# SCH_Hackpad-c-pad_2026-07-27.net
KiCad netlist of a schematic drawn in EasyEDA
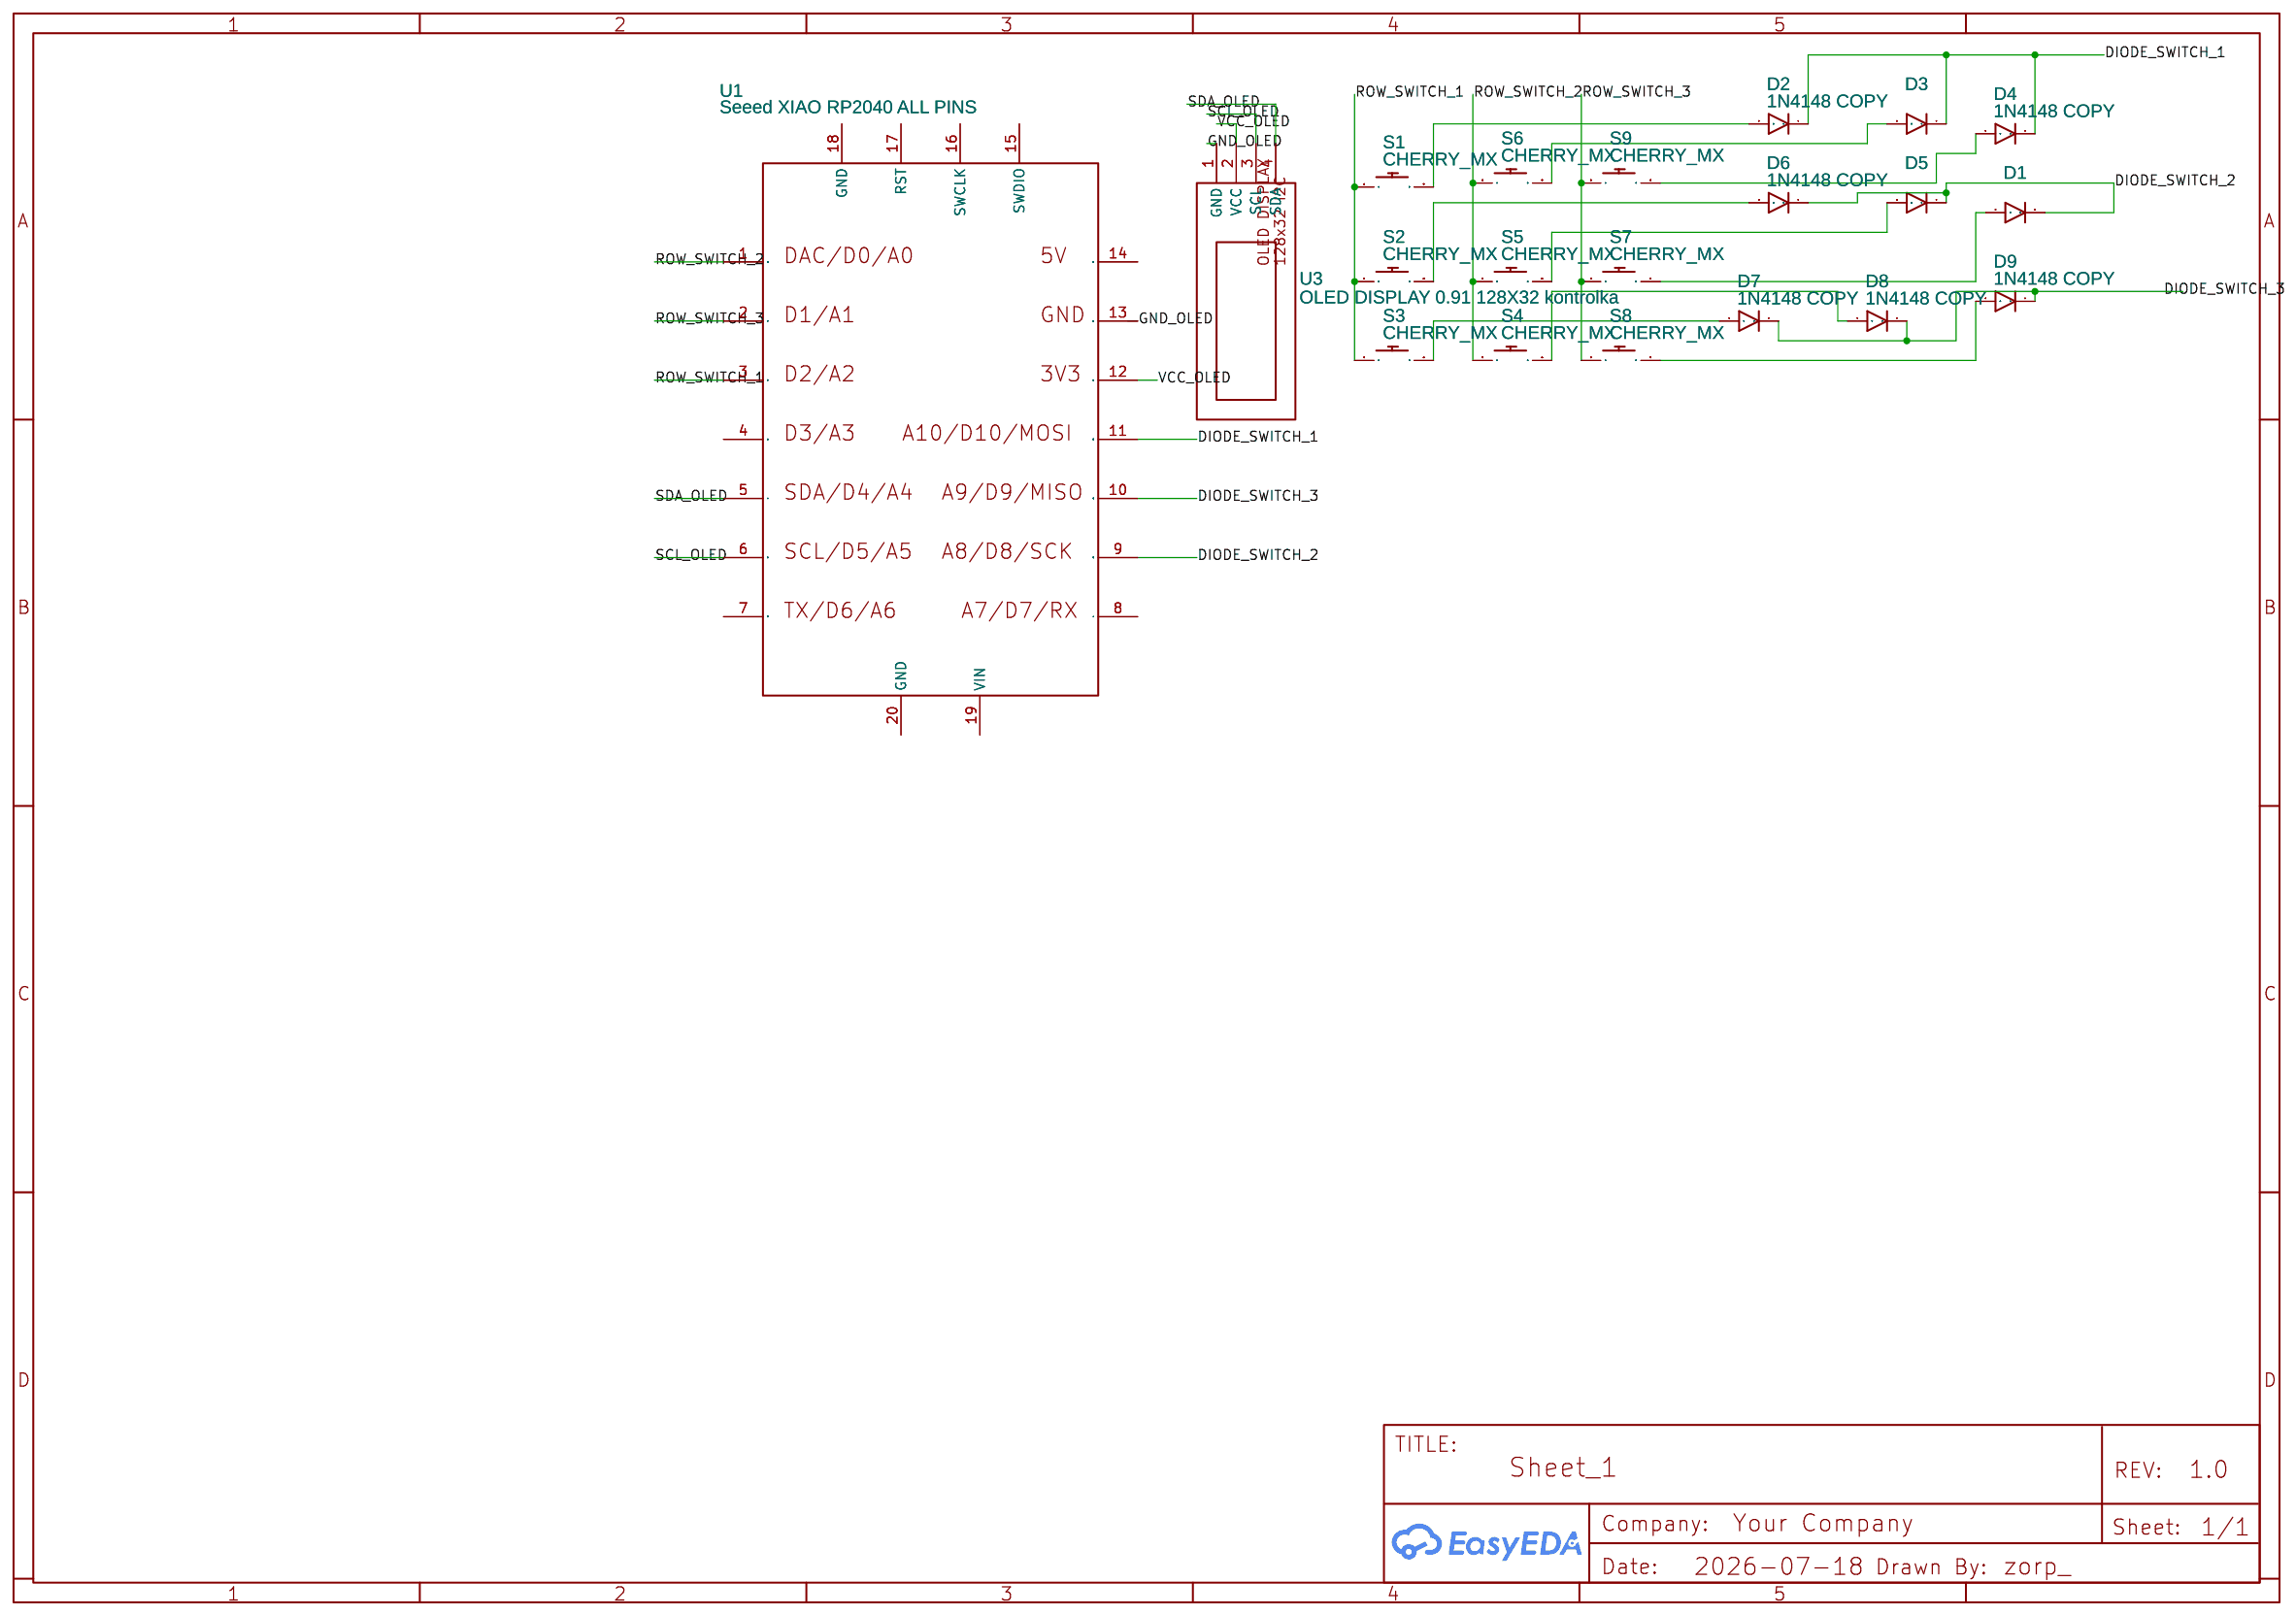
[diagram p0: schematic sheet]

(export (version "E")
  (design (tool "Eeschema 10.0.6"))
  (components
    (comp (ref "D1") (value "1N4148 COPY") (libsource (lib "") (part "1N4148 COPY")))
    (comp (ref "D2") (value "1N4148 COPY") (libsource (lib "") (part "1N4148 COPY")))
    (comp (ref "D3") (value "1N4148 COPY") (libsource (lib "") (part "1N4148 COPY")))
    (comp (ref "D4") (value "1N4148 COPY") (libsource (lib "") (part "1N4148 COPY")))
    (comp (ref "D5") (value "1N4148 COPY") (libsource (lib "") (part "1N4148 COPY")))
    (comp (ref "D6") (value "1N4148 COPY") (libsource (lib "") (part "1N4148 COPY")))
    (comp (ref "D7") (value "1N4148 COPY") (libsource (lib "") (part "1N4148 COPY")))
    (comp (ref "D8") (value "1N4148 COPY") (libsource (lib "") (part "1N4148 COPY")))
    (comp (ref "D9") (value "1N4148 COPY") (libsource (lib "") (part "1N4148 COPY")))
    (comp (ref "S1") (value "CHERRY_MX") (libsource (lib "") (part "CHERRY_MX")))
    (comp (ref "S2") (value "CHERRY_MX") (libsource (lib "") (part "CHERRY_MX")))
    (comp (ref "S3") (value "CHERRY_MX") (libsource (lib "") (part "CHERRY_MX")))
    (comp (ref "S4") (value "CHERRY_MX") (libsource (lib "") (part "CHERRY_MX")))
    (comp (ref "S5") (value "CHERRY_MX") (libsource (lib "") (part "CHERRY_MX")))
    (comp (ref "S6") (value "CHERRY_MX") (libsource (lib "") (part "CHERRY_MX")))
    (comp (ref "S7") (value "CHERRY_MX") (libsource (lib "") (part "CHERRY_MX")))
    (comp (ref "S8") (value "CHERRY_MX") (libsource (lib "") (part "CHERRY_MX")))
    (comp (ref "S9") (value "CHERRY_MX") (libsource (lib "") (part "CHERRY_MX")))
    (comp (ref "U1")
      (value "Seeed XIAO RP2040 ALL PINS")
      (fields (field (name "Manufacturer Part") "102010328") (field (name "Manufacturer") "Seeedstudio"))
      (libsource (lib "") (part "Seeed XIAO RP2040 ALL PINS"))
    )
    (comp (ref "U3")
      (value "OLED DISPLAY 0.91 128X32 kontrolka")
      (libsource (lib "") (part "OLED DISPLAY 0.91 128X32 kontrolka"))
    )
  )
  (nets
    (net (code "1") (name "/DIODE_SWITCH_1") (class "Default")
      (node (ref "D2") (pin "1") (pinfunction "1_1") (pintype "unspecified"))
      (node (ref "D3") (pin "1") (pinfunction "1_1") (pintype "unspecified"))
      (node (ref "D4") (pin "1") (pinfunction "1_1") (pintype "unspecified"))
      (node (ref "U1") (pin "11") (pinfunction "10_11") (pintype "unspecified"))
    )
    (net (code "2") (name "/DIODE_SWITCH_2") (class "Default")
      (node (ref "D1") (pin "1") (pinfunction "1_1") (pintype "unspecified"))
      (node (ref "D5") (pin "1") (pinfunction "1_1") (pintype "unspecified"))
      (node (ref "D6") (pin "1") (pinfunction "1_1") (pintype "unspecified"))
      (node (ref "U1") (pin "9") (pinfunction "8_9") (pintype "unspecified"))
    )
    (net (code "3") (name "/DIODE_SWITCH_3") (class "Default")
      (node (ref "D7") (pin "1") (pinfunction "1_1") (pintype "unspecified"))
      (node (ref "D8") (pin "1") (pinfunction "1_1") (pintype "unspecified"))
      (node (ref "D9") (pin "1") (pinfunction "1_1") (pintype "unspecified"))
      (node (ref "U1") (pin "10") (pinfunction "9_10") (pintype "unspecified"))
    )
    (net (code "4") (name "/GND_OLED") (class "Default")
      (node (ref "U1") (pin "13") (pinfunction "12_13") (pintype "unspecified"))
      (node (ref "U3") (pin "1") (pinfunction "GND_1") (pintype "passive"))
    )
    (net (code "5") (name "/ROW_SWITCH_1") (class "Default")
      (node (ref "S1") (pin "S1") (pinfunction "1_S1") (pintype "bidirectional"))
      (node (ref "S2") (pin "S1") (pinfunction "1_S1") (pintype "bidirectional"))
      (node (ref "S3") (pin "S1") (pinfunction "1_S1") (pintype "bidirectional"))
      (node (ref "U1") (pin "3") (pinfunction "2_3") (pintype "unspecified"))
    )
    (net (code "6") (name "/ROW_SWITCH_2") (class "Default")
      (node (ref "S4") (pin "S1") (pinfunction "1_S1") (pintype "bidirectional"))
      (node (ref "S5") (pin "S1") (pinfunction "1_S1") (pintype "bidirectional"))
      (node (ref "S6") (pin "S1") (pinfunction "1_S1") (pintype "bidirectional"))
      (node (ref "U1") (pin "1") (pinfunction "0_1") (pintype "unspecified"))
    )
    (net (code "7") (name "/ROW_SWITCH_3") (class "Default")
      (node (ref "S7") (pin "S1") (pinfunction "1_S1") (pintype "bidirectional"))
      (node (ref "S8") (pin "S1") (pinfunction "1_S1") (pintype "bidirectional"))
      (node (ref "S9") (pin "S1") (pinfunction "1_S1") (pintype "bidirectional"))
      (node (ref "U1") (pin "2") (pinfunction "1_2") (pintype "unspecified"))
    )
    (net (code "8") (name "/SCL_OLED") (class "Default")
      (node (ref "U1") (pin "6") (pinfunction "5_6") (pintype "unspecified"))
      (node (ref "U3") (pin "3") (pinfunction "SCL_3") (pintype "input"))
    )
    (net (code "9") (name "/SDA_OLED") (class "Default")
      (node (ref "U1") (pin "5") (pinfunction "4_5") (pintype "unspecified"))
      (node (ref "U3") (pin "4") (pinfunction "SDA_4") (pintype "input"))
    )
    (net (code "10") (name "/VCC_OLED") (class "Default")
      (node (ref "U1") (pin "12") (pinfunction "11_12") (pintype "unspecified"))
      (node (ref "U3") (pin "2") (pinfunction "VCC_2") (pintype "passive"))
    )
    (net (code "11") (name "Net-(S1-2)") (class "Default")
      (node (ref "D2") (pin "2") (pinfunction "2_2") (pintype "unspecified"))
      (node (ref "S1") (pin "S2") (pinfunction "2_S2") (pintype "bidirectional"))
    )
    (net (code "12") (name "Net-(S2-2)") (class "Default")
      (node (ref "D6") (pin "2") (pinfunction "2_2") (pintype "unspecified"))
      (node (ref "S2") (pin "S2") (pinfunction "2_S2") (pintype "bidirectional"))
    )
    (net (code "13") (name "Net-(S3-2)") (class "Default")
      (node (ref "D7") (pin "2") (pinfunction "2_2") (pintype "unspecified"))
      (node (ref "S3") (pin "S2") (pinfunction "2_S2") (pintype "bidirectional"))
    )
    (net (code "14") (name "Net-(S4-2)") (class "Default")
      (node (ref "D8") (pin "2") (pinfunction "2_2") (pintype "unspecified"))
      (node (ref "S4") (pin "S2") (pinfunction "2_S2") (pintype "bidirectional"))
    )
    (net (code "15") (name "Net-(S5-2)") (class "Default")
      (node (ref "D5") (pin "2") (pinfunction "2_2") (pintype "unspecified"))
      (node (ref "S5") (pin "S2") (pinfunction "2_S2") (pintype "bidirectional"))
    )
    (net (code "16") (name "Net-(S6-2)") (class "Default")
      (node (ref "D3") (pin "2") (pinfunction "2_2") (pintype "unspecified"))
      (node (ref "S6") (pin "S2") (pinfunction "2_S2") (pintype "bidirectional"))
    )
    (net (code "17") (name "Net-(S7-2)") (class "Default")
      (node (ref "D1") (pin "2") (pinfunction "2_2") (pintype "unspecified"))
      (node (ref "S7") (pin "S2") (pinfunction "2_S2") (pintype "bidirectional"))
    )
    (net (code "18") (name "Net-(S8-2)") (class "Default")
      (node (ref "D9") (pin "2") (pinfunction "2_2") (pintype "unspecified"))
      (node (ref "S8") (pin "S2") (pinfunction "2_S2") (pintype "bidirectional"))
    )
    (net (code "19") (name "Net-(S9-2)") (class "Default")
      (node (ref "D4") (pin "2") (pinfunction "2_2") (pintype "unspecified"))
      (node (ref "S9") (pin "S2") (pinfunction "2_S2") (pintype "bidirectional"))
    )
    (net (code "20") (name "unconnected-(U1-3-Pad4)") (class "Default")
      (node (ref "U1") (pin "4") (pinfunction "3_4") (pintype "unspecified"))
    )
    (net (code "21") (name "unconnected-(U1-6-Pad7)") (class "Default")
      (node (ref "U1") (pin "7") (pinfunction "6_7") (pintype "unspecified"))
    )
    (net (code "22") (name "unconnected-(U1-7-Pad8)") (class "Default")
      (node (ref "U1") (pin "8") (pinfunction "7_8") (pintype "unspecified"))
    )
    (net (code "23") (name "unconnected-(U1-13-Pad14)") (class "Default")
      (node (ref "U1") (pin "14") (pinfunction "13_14") (pintype "unspecified"))
    )
    (net (code "24") (name "unconnected-(U1-GND-Pad18)") (class "Default")
      (node (ref "U1") (pin "18") (pinfunction "GND_18") (pintype "unspecified"))
    )
    (net (code "25") (name "unconnected-(U1-GND-Pad20)") (class "Default")
      (node (ref "U1") (pin "20") (pinfunction "GND_20") (pintype "unspecified"))
    )
    (net (code "26") (name "unconnected-(U1-RST-Pad17)") (class "Default")
      (node (ref "U1") (pin "17") (pinfunction "RST_17") (pintype "unspecified"))
    )
    (net (code "27") (name "unconnected-(U1-SWCLK-Pad16)") (class "Default")
      (node (ref "U1") (pin "16") (pinfunction "SWCLK_16") (pintype "unspecified"))
    )
    (net (code "28") (name "unconnected-(U1-SWDIO-Pad15)") (class "Default")
      (node (ref "U1") (pin "15") (pinfunction "SWDIO_15") (pintype "unspecified"))
    )
    (net (code "29") (name "unconnected-(U1-VIN-Pad19)") (class "Default")
      (node (ref "U1") (pin "19") (pinfunction "VIN_19") (pintype "unspecified"))
    )
  )
)
